# ExternalConnections.net
KiCad netlist of a schematic drawn in Altium Designer
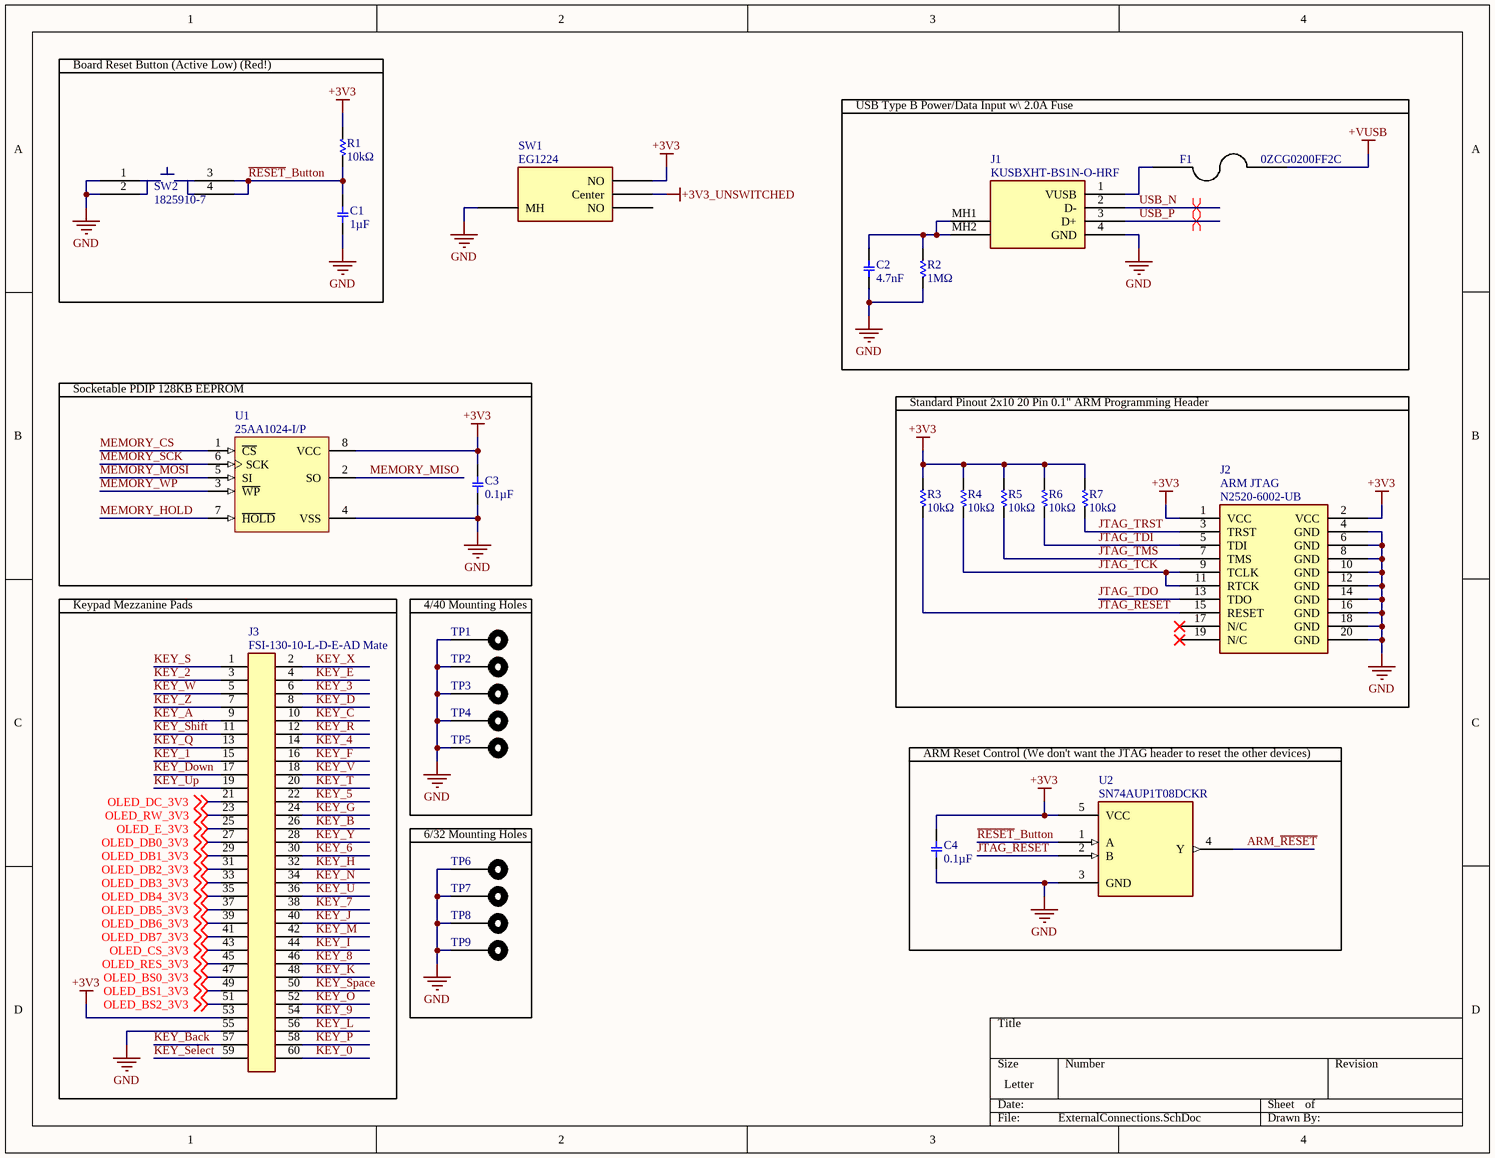
[diagram p0: ExternalConnections.SchDoc]

(export (version "E")
  (design (tool "Eeschema 10.0.6"))
  (components
    (comp (ref "C1")
      (value "1µF")
      (footprint "C0805(2012)_NP_med")
      (description "SMT Capacitor")
      (fields (field (name "TOLERANCE") "X7R"))
      (libsource (lib "ChipComponents") (part "CPN_SMT"))
    )
    (comp (ref "C2")
      (value "4.7nF")
      (footprint "C0805(2012)_NP_med")
      (description "SMT Capacitor")
      (fields (field (name "TOLERANCE") "X7R"))
      (libsource (lib "ChipComponents") (part "CPN_SMT"))
    )
    (comp (ref "C3")
      (value "0.1µF")
      (footprint "C0805(2012)_NP_med")
      (description "SMT Capacitor")
      (fields (field (name "TOLERANCE") "X7R"))
      (libsource (lib "ChipComponents") (part "CPN_SMT"))
    )
    (comp (ref "C4")
      (value "0.1µF")
      (footprint "C0805(2012)_NP_med")
      (description "SMT Capacitor")
      (fields (field (name "TOLERANCE") "X7R"))
      (libsource (lib "ChipComponents") (part "CPN_SMT"))
    )
    (comp (ref "F1")
      (value "Bel 0ZCG0200FF2C")
      (footprint "C1812(4532)_NP_med")
      (description "PTC RESTTBLE 2.0A 8V CHIP 1812")
      (fields
        (field (name "MANUFACTURER") "Bel Fuse Inc.")
        (field (name "MANUFACTURER PART NUMBER") "0ZCG0200FF2C")
      )
      (libsource (lib "RFIDSchematicLibrary") (part "Bel 0ZCG0200FF2C"))
    )
    (comp (ref "J1")
      (value "KUSBXHT-BS1N-O-HRF")
      (footprint "Kycon KUSBXHT-BS1N-O-HRF")
      (description "TYPE B ORANGE HIGH TEMP/RETENTION")
      (fields (field (name "MANUFACTURER") "Kycon"))
      (libsource (lib "RFIDSchematicLibrary") (part "Kycon KUSBXHT-BS1N-O-HRF"))
    )
    (comp (ref "J2")
      (value "ARM JTAG")
      (footprint "3M 2520-6002UB")
      (description "Standard 20-Pin Pinout")
      (fields (field (name "MANUFACTURER") "3M") (field (name "MANUFACTURER PART NUMBER") "N2520-6002-UB"))
      (libsource (lib "RFIDSchematicLibrary") (part "20-Pin ARM JTAG Programming Header"))
    )
    (comp (ref "J3")
      (value "FSI-130-10-L-D-E-AD Mate")
      (footprint "FSI-130-10-L-D-E-AD - Mate")
      (description "CONN INTERFACE ONE PC 1MM 60POS")
      (libsource (lib "RFIDSchematicLibrary") (part "Samtec FSI-130-10-L-D-E-AD Mate"))
    )
    (comp (ref "R1")
      (value "10kΩ")
      (footprint "R0805(2012)_med")
      (description "SMT resistor")
      (fields (field (name "TOLERANCE") "1%"))
      (libsource (lib "ChipComponents") (part "RES_SMT"))
    )
    (comp (ref "R2")
      (value "1MΩ")
      (footprint "R0805(2012)_med")
      (description "SMT resistor")
      (fields (field (name "TOLERANCE") "1%"))
      (libsource (lib "ChipComponents") (part "RES_SMT"))
    )
    (comp (ref "R3")
      (value "10kΩ")
      (footprint "R0805(2012)_med")
      (description "SMT resistor")
      (fields (field (name "TOLERANCE") "1%"))
      (libsource (lib "ChipComponents") (part "RES_SMT"))
    )
    (comp (ref "R4")
      (value "10kΩ")
      (footprint "R0805(2012)_med")
      (description "SMT resistor")
      (fields (field (name "TOLERANCE") "1%"))
      (libsource (lib "ChipComponents") (part "RES_SMT"))
    )
    (comp (ref "R5")
      (value "10kΩ")
      (footprint "R0805(2012)_med")
      (description "SMT resistor")
      (fields (field (name "TOLERANCE") "1%"))
      (libsource (lib "ChipComponents") (part "RES_SMT"))
    )
    (comp (ref "R6")
      (value "10kΩ")
      (footprint "R0805(2012)_med")
      (description "SMT resistor")
      (fields (field (name "TOLERANCE") "1%"))
      (libsource (lib "ChipComponents") (part "RES_SMT"))
    )
    (comp (ref "R7")
      (value "10kΩ")
      (footprint "R0805(2012)_med")
      (description "SMT resistor")
      (fields (field (name "TOLERANCE") "1%"))
      (libsource (lib "ChipComponents") (part "RES_SMT"))
    )
    (comp (ref "SW1")
      (value "E-Switch EG1224")
      (footprint "E-Switch EG1224")
      (description "SWITCH SLIDE SPDT 500MA 15V")
      (fields (field (name "MANUFACTURER") "E-Switch") (field (name "MANUFACTURER PART NUMBER") "EG1224"))
      (libsource (lib "RFIDSchematicLibrary") (part "E-Switch EG1224"))
    )
    (comp (ref "SW2")
      (value "1825910-7")
      (footprint "TE 1825910-6")
      (description "SWITCH TACTILE SPST-NO 0.05A 24V")
      (fields
        (field (name "MANUFACTURER") "TE Connectivity Alcoswitch Switches")
        (field (name "MANUFACTURER PART NUMBER") "1825910-6")
      )
      (libsource (lib "RFIDSchematicLibrary") (part "TE 1825910-6"))
    )
    (comp (ref "TP1")
      (value "Testpoint")
      (footprint "4-40 HOLE")
      (libsource (lib "RFIDSchematicLibrary") (part "Testpoint"))
    )
    (comp (ref "TP2")
      (value "Testpoint")
      (footprint "4-40 HOLE")
      (libsource (lib "RFIDSchematicLibrary") (part "Testpoint"))
    )
    (comp (ref "TP3")
      (value "Testpoint")
      (footprint "4-40 HOLE")
      (libsource (lib "RFIDSchematicLibrary") (part "Testpoint"))
    )
    (comp (ref "TP4")
      (value "Testpoint")
      (footprint "4-40 HOLE")
      (libsource (lib "RFIDSchematicLibrary") (part "Testpoint"))
    )
    (comp (ref "TP5")
      (value "Testpoint")
      (footprint "4-40 HOLE")
      (libsource (lib "RFIDSchematicLibrary") (part "Testpoint"))
    )
    (comp (ref "TP6")
      (value "Testpoint")
      (footprint "6-32 Hole")
      (libsource (lib "RFIDSchematicLibrary") (part "Testpoint"))
    )
    (comp (ref "TP7")
      (value "Testpoint")
      (footprint "6-32 Hole")
      (libsource (lib "RFIDSchematicLibrary") (part "Testpoint"))
    )
    (comp (ref "TP8")
      (value "Testpoint")
      (footprint "6-32 Hole")
      (libsource (lib "RFIDSchematicLibrary") (part "Testpoint"))
    )
    (comp (ref "TP9")
      (value "Testpoint")
      (footprint "6-32 Hole")
      (libsource (lib "RFIDSchematicLibrary") (part "Testpoint"))
    )
    (comp (ref "U1")
      (value "25AA1024-I/P")
      (footprint "PDIP300-P8")
      (description "1 Mbit SPI Bus Serial EEPROM, 8-Pin PDIP, Industrial Temperature")
      (fields (field (name "MANUFACTURER") "Microchip"))
      (libsource (lib "Microchip SPI Serial EEPROM") (part "25AA1024-I/P"))
    )
    (comp (ref "U2")
      (value "TI SN74AUP1T08DCKR")
      (footprint "TI 5 Pin DCK (R-PDSO-G5)")
      (description "IC GATE AND 1CH 2-INP SC-70-5")
      (fields
        (field (name "MANUFACTURER") "Texas Instruments")
        (field (name "MANUFACTURER PART NUMBER") "SN74AUP1T08DCKR")
      )
      (libsource (lib "RFIDSchematicLibrary") (part "TI SN74AUP1T08DCKR"))
    )
  )
  (nets
    (net (code "1") (name "+3V3") (class "Default")
      (node (ref "C3") (pin "1") (pinfunction "1_1") (pintype "passive"))
      (node (ref "C4") (pin "1") (pinfunction "1_1") (pintype "passive"))
      (node (ref "J2") (pin "1") (pinfunction "VCC_1") (pintype "passive"))
      (node (ref "J2") (pin "2") (pinfunction "VCC_2") (pintype "passive"))
      (node (ref "J3") (pin "53") (pinfunction "53_53") (pintype "passive"))
      (node (ref "R1") (pin "1") (pinfunction "1_1") (pintype "passive"))
      (node (ref "R3") (pin "1") (pinfunction "1_1") (pintype "passive"))
      (node (ref "R4") (pin "1") (pinfunction "1_1") (pintype "passive"))
      (node (ref "R5") (pin "1") (pinfunction "1_1") (pintype "passive"))
      (node (ref "R6") (pin "1") (pinfunction "1_1") (pintype "passive"))
      (node (ref "R7") (pin "1") (pinfunction "1_1") (pintype "passive"))
      (node (ref "SW1") (pin "1") (pinfunction "NO_1") (pintype "passive"))
      (node (ref "U1") (pin "8") (pinfunction "VCC_8") (pintype "power_in"))
      (node (ref "U2") (pin "5") (pinfunction "VCC_5") (pintype "power_in"))
    )
    (net (code "2") (name "+3V3_UNSWITCHED") (class "Default")
      (node (ref "SW1") (pin "2") (pinfunction "Center_2") (pintype "passive"))
    )
    (net (code "3") (name "+VUSB") (class "Default")
      (node (ref "F1") (pin "2") (pinfunction "2_2") (pintype "passive"))
    )
    (net (code "4") (name "/ARM_~{RESET}") (class "Default")
      (node (ref "U2") (pin "4") (pinfunction "Y_4") (pintype "output"))
    )
    (net (code "5") (name "/JTAG_TCK") (class "Default")
      (node (ref "J2") (pin "11") (pinfunction "RTCK_11") (pintype "passive"))
      (node (ref "J2") (pin "9") (pinfunction "TCLK_9") (pintype "passive"))
      (node (ref "R4") (pin "2") (pinfunction "2_2") (pintype "passive"))
    )
    (net (code "6") (name "/JTAG_TDI") (class "Default")
      (node (ref "J2") (pin "5") (pinfunction "TDI_5") (pintype "passive"))
      (node (ref "R6") (pin "2") (pinfunction "2_2") (pintype "passive"))
    )
    (net (code "7") (name "/JTAG_TDO") (class "Default")
      (node (ref "J2") (pin "13") (pinfunction "TDO_13") (pintype "passive"))
    )
    (net (code "8") (name "/JTAG_TMS") (class "Default")
      (node (ref "J2") (pin "7") (pinfunction "TMS_7") (pintype "passive"))
      (node (ref "R5") (pin "2") (pinfunction "2_2") (pintype "passive"))
    )
    (net (code "9") (name "/JTAG_TRST") (class "Default")
      (node (ref "J2") (pin "3") (pinfunction "TRST_3") (pintype "passive"))
      (node (ref "R7") (pin "2") (pinfunction "2_2") (pintype "passive"))
    )
    (net (code "10") (name "/JTAG_~{RESET}") (class "Default")
      (node (ref "J2") (pin "15") (pinfunction "RESET_15") (pintype "passive"))
      (node (ref "R3") (pin "2") (pinfunction "2_2") (pintype "passive"))
      (node (ref "U2") (pin "2") (pinfunction "B_2") (pintype "input"))
    )
    (net (code "11") (name "/KEY_0") (class "Default")
      (node (ref "J3") (pin "60") (pinfunction "60_60") (pintype "passive"))
    )
    (net (code "12") (name "/KEY_1") (class "Default")
      (node (ref "J3") (pin "15") (pinfunction "15_15") (pintype "passive"))
    )
    (net (code "13") (name "/KEY_2") (class "Default")
      (node (ref "J3") (pin "3") (pinfunction "3_3") (pintype "passive"))
    )
    (net (code "14") (name "/KEY_3") (class "Default")
      (node (ref "J3") (pin "6") (pinfunction "6_6") (pintype "passive"))
    )
    (net (code "15") (name "/KEY_4") (class "Default")
      (node (ref "J3") (pin "14") (pinfunction "14_14") (pintype "passive"))
    )
    (net (code "16") (name "/KEY_5") (class "Default")
      (node (ref "J3") (pin "22") (pinfunction "22_22") (pintype "passive"))
    )
    (net (code "17") (name "/KEY_6") (class "Default")
      (node (ref "J3") (pin "30") (pinfunction "30_30") (pintype "passive"))
    )
    (net (code "18") (name "/KEY_7") (class "Default")
      (node (ref "J3") (pin "38") (pinfunction "38_38") (pintype "passive"))
    )
    (net (code "19") (name "/KEY_8") (class "Default")
      (node (ref "J3") (pin "46") (pinfunction "46_46") (pintype "passive"))
    )
    (net (code "20") (name "/KEY_9") (class "Default")
      (node (ref "J3") (pin "54") (pinfunction "54_54") (pintype "passive"))
    )
    (net (code "21") (name "/KEY_A") (class "Default")
      (node (ref "J3") (pin "9") (pinfunction "9_9") (pintype "passive"))
    )
    (net (code "22") (name "/KEY_B") (class "Default")
      (node (ref "J3") (pin "26") (pinfunction "26_26") (pintype "passive"))
    )
    (net (code "23") (name "/KEY_Back") (class "Default")
      (node (ref "J3") (pin "57") (pinfunction "57_57") (pintype "passive"))
    )
    (net (code "24") (name "/KEY_C") (class "Default")
      (node (ref "J3") (pin "10") (pinfunction "10_10") (pintype "passive"))
    )
    (net (code "25") (name "/KEY_D") (class "Default")
      (node (ref "J3") (pin "8") (pinfunction "8_8") (pintype "passive"))
    )
    (net (code "26") (name "/KEY_Down") (class "Default")
      (node (ref "J3") (pin "17") (pinfunction "17_17") (pintype "passive"))
    )
    (net (code "27") (name "/KEY_E") (class "Default")
      (node (ref "J3") (pin "4") (pinfunction "4_4") (pintype "passive"))
    )
    (net (code "28") (name "/KEY_F") (class "Default")
      (node (ref "J3") (pin "16") (pinfunction "16_16") (pintype "passive"))
    )
    (net (code "29") (name "/KEY_G") (class "Default")
      (node (ref "J3") (pin "24") (pinfunction "24_24") (pintype "passive"))
    )
    (net (code "30") (name "/KEY_H") (class "Default")
      (node (ref "J3") (pin "32") (pinfunction "32_32") (pintype "passive"))
    )
    (net (code "31") (name "/KEY_I") (class "Default")
      (node (ref "J3") (pin "44") (pinfunction "44_44") (pintype "passive"))
    )
    (net (code "32") (name "/KEY_J") (class "Default")
      (node (ref "J3") (pin "40") (pinfunction "40_40") (pintype "passive"))
    )
    (net (code "33") (name "/KEY_K") (class "Default")
      (node (ref "J3") (pin "48") (pinfunction "48_48") (pintype "passive"))
    )
    (net (code "34") (name "/KEY_L") (class "Default")
      (node (ref "J3") (pin "56") (pinfunction "56_56") (pintype "passive"))
    )
    (net (code "35") (name "/KEY_M") (class "Default")
      (node (ref "J3") (pin "42") (pinfunction "42_42") (pintype "passive"))
    )
    (net (code "36") (name "/KEY_N") (class "Default")
      (node (ref "J3") (pin "34") (pinfunction "34_34") (pintype "passive"))
    )
    (net (code "37") (name "/KEY_O") (class "Default")
      (node (ref "J3") (pin "52") (pinfunction "52_52") (pintype "passive"))
    )
    (net (code "38") (name "/KEY_P") (class "Default")
      (node (ref "J3") (pin "58") (pinfunction "58_58") (pintype "passive"))
    )
    (net (code "39") (name "/KEY_Q") (class "Default")
      (node (ref "J3") (pin "13") (pinfunction "13_13") (pintype "passive"))
    )
    (net (code "40") (name "/KEY_R") (class "Default")
      (node (ref "J3") (pin "12") (pinfunction "12_12") (pintype "passive"))
    )
    (net (code "41") (name "/KEY_S") (class "Default")
      (node (ref "J3") (pin "1") (pinfunction "1_1") (pintype "passive"))
    )
    (net (code "42") (name "/KEY_Select") (class "Default")
      (node (ref "J3") (pin "59") (pinfunction "59_59") (pintype "passive"))
    )
    (net (code "43") (name "/KEY_Shift") (class "Default")
      (node (ref "J3") (pin "11") (pinfunction "11_11") (pintype "passive"))
    )
    (net (code "44") (name "/KEY_Space") (class "Default")
      (node (ref "J3") (pin "50") (pinfunction "50_50") (pintype "passive"))
    )
    (net (code "45") (name "/KEY_T") (class "Default")
      (node (ref "J3") (pin "20") (pinfunction "20_20") (pintype "passive"))
    )
    (net (code "46") (name "/KEY_U") (class "Default")
      (node (ref "J3") (pin "36") (pinfunction "36_36") (pintype "passive"))
    )
    (net (code "47") (name "/KEY_Up") (class "Default")
      (node (ref "J3") (pin "19") (pinfunction "19_19") (pintype "passive"))
    )
    (net (code "48") (name "/KEY_V") (class "Default")
      (node (ref "J3") (pin "18") (pinfunction "18_18") (pintype "passive"))
    )
    (net (code "49") (name "/KEY_W") (class "Default")
      (node (ref "J3") (pin "5") (pinfunction "5_5") (pintype "passive"))
    )
    (net (code "50") (name "/KEY_X") (class "Default")
      (node (ref "J3") (pin "2") (pinfunction "2_2") (pintype "passive"))
    )
    (net (code "51") (name "/KEY_Y") (class "Default")
      (node (ref "J3") (pin "28") (pinfunction "28_28") (pintype "passive"))
    )
    (net (code "52") (name "/KEY_Z") (class "Default")
      (node (ref "J3") (pin "7") (pinfunction "7_7") (pintype "passive"))
    )
    (net (code "53") (name "/MEMORY_CS") (class "Default")
      (node (ref "U1") (pin "1") (pinfunction "~{CS}_1") (pintype "input"))
    )
    (net (code "54") (name "/MEMORY_HOLD") (class "Default")
      (node (ref "U1") (pin "7") (pinfunction "~{HOLD}_7") (pintype "input"))
    )
    (net (code "55") (name "/MEMORY_MISO") (class "Default")
      (node (ref "U1") (pin "2") (pinfunction "SO_2") (pintype "tri_state"))
    )
    (net (code "56") (name "/MEMORY_MOSI") (class "Default")
      (node (ref "U1") (pin "5") (pinfunction "SI_5") (pintype "input"))
    )
    (net (code "57") (name "/MEMORY_SCK") (class "Default")
      (node (ref "U1") (pin "6") (pinfunction "SCK_6") (pintype "input"))
    )
    (net (code "58") (name "/MEMORY_WP") (class "Default")
      (node (ref "U1") (pin "3") (pinfunction "~{WP}_3") (pintype "input"))
    )
    (net (code "59") (name "/USB_N") (class "Default")
      (node (ref "J1") (pin "2") (pinfunction "D-_2") (pintype "passive"))
    )
    (net (code "60") (name "/USB_P") (class "Default")
      (node (ref "J1") (pin "3") (pinfunction "D+_3") (pintype "passive"))
    )
    (net (code "61") (name "/~{RESET}_Button") (class "Default")
      (node (ref "C1") (pin "1") (pinfunction "1_1") (pintype "passive"))
      (node (ref "R1") (pin "2") (pinfunction "2_2") (pintype "passive"))
      (node (ref "SW2") (pin "3") (pinfunction "3_3") (pintype "passive"))
      (node (ref "SW2") (pin "4") (pinfunction "4_4") (pintype "passive"))
      (node (ref "U2") (pin "1") (pinfunction "A_1") (pintype "input"))
    )
    (net (code "62") (name "GND") (class "Default")
      (node (ref "C1") (pin "2") (pinfunction "2_2") (pintype "passive"))
      (node (ref "C2") (pin "2") (pinfunction "2_2") (pintype "passive"))
      (node (ref "C3") (pin "2") (pinfunction "2_2") (pintype "passive"))
      (node (ref "C4") (pin "2") (pinfunction "2_2") (pintype "passive"))
      (node (ref "J1") (pin "4") (pinfunction "GND_4") (pintype "passive"))
      (node (ref "J2") (pin "10") (pinfunction "GND_10") (pintype "passive"))
      (node (ref "J2") (pin "12") (pinfunction "GND_12") (pintype "passive"))
      (node (ref "J2") (pin "14") (pinfunction "GND_14") (pintype "passive"))
      (node (ref "J2") (pin "16") (pinfunction "GND_16") (pintype "passive"))
      (node (ref "J2") (pin "18") (pinfunction "GND_18") (pintype "passive"))
      (node (ref "J2") (pin "20") (pinfunction "GND_20") (pintype "passive"))
      (node (ref "J2") (pin "4") (pinfunction "GND_4") (pintype "passive"))
      (node (ref "J2") (pin "6") (pinfunction "GND_6") (pintype "passive"))
      (node (ref "J2") (pin "8") (pinfunction "GND_8") (pintype "passive"))
      (node (ref "J3") (pin "55") (pinfunction "55_55") (pintype "passive"))
      (node (ref "R2") (pin "2") (pinfunction "2_2") (pintype "passive"))
      (node (ref "SW1") (pin "4") (pinfunction "MH_4") (pintype "passive"))
      (node (ref "SW2") (pin "1") (pinfunction "1_1") (pintype "passive"))
      (node (ref "SW2") (pin "2") (pinfunction "2_2") (pintype "passive"))
      (node (ref "TP1") (pin "1") (pinfunction "1_1") (pintype "passive"))
      (node (ref "TP2") (pin "1") (pinfunction "1_1") (pintype "passive"))
      (node (ref "TP3") (pin "1") (pinfunction "1_1") (pintype "passive"))
      (node (ref "TP4") (pin "1") (pinfunction "1_1") (pintype "passive"))
      (node (ref "TP5") (pin "1") (pinfunction "1_1") (pintype "passive"))
      (node (ref "TP6") (pin "1") (pinfunction "1_1") (pintype "passive"))
      (node (ref "TP7") (pin "1") (pinfunction "1_1") (pintype "passive"))
      (node (ref "TP8") (pin "1") (pinfunction "1_1") (pintype "passive"))
      (node (ref "TP9") (pin "1") (pinfunction "1_1") (pintype "passive"))
      (node (ref "U1") (pin "4") (pinfunction "VSS_4") (pintype "power_in"))
      (node (ref "U2") (pin "3") (pinfunction "GND_3") (pintype "power_in"))
    )
    (net (code "63") (name "Net-(C2-Pad1)") (class "Default")
      (node (ref "C2") (pin "1") (pinfunction "1_1") (pintype "passive"))
      (node (ref "J1") (pin "MH1") (pinfunction "MH1_MH1") (pintype "passive"))
      (node (ref "J1") (pin "MH2") (pinfunction "MH2_MH2") (pintype "passive"))
      (node (ref "R2") (pin "1") (pinfunction "1_1") (pintype "passive"))
    )
    (net (code "64") (name "Net-(J1-VUSB)") (class "Default")
      (node (ref "F1") (pin "1") (pinfunction "1_1") (pintype "passive"))
      (node (ref "J1") (pin "1") (pinfunction "VUSB_1") (pintype "passive"))
    )
    (net (code "65") (name "OLED_BS0_3V3") (class "Default")
      (node (ref "J3") (pin "47") (pinfunction "47_47") (pintype "passive"))
    )
    (net (code "66") (name "OLED_BS1_3V3") (class "Default")
      (node (ref "J3") (pin "49") (pinfunction "49_49") (pintype "passive"))
    )
    (net (code "67") (name "OLED_BS2_3V3") (class "Default")
      (node (ref "J3") (pin "51") (pinfunction "51_51") (pintype "passive"))
    )
    (net (code "68") (name "OLED_CS_3V3") (class "Default")
      (node (ref "J3") (pin "43") (pinfunction "43_43") (pintype "passive"))
    )
    (net (code "69") (name "OLED_DB0_3V3") (class "Default")
      (node (ref "J3") (pin "27") (pinfunction "27_27") (pintype "passive"))
    )
    (net (code "70") (name "OLED_DB1_3V3") (class "Default")
      (node (ref "J3") (pin "29") (pinfunction "29_29") (pintype "passive"))
    )
    (net (code "71") (name "OLED_DB2_3V3") (class "Default")
      (node (ref "J3") (pin "31") (pinfunction "31_31") (pintype "passive"))
    )
    (net (code "72") (name "OLED_DB3_3V3") (class "Default")
      (node (ref "J3") (pin "33") (pinfunction "33_33") (pintype "passive"))
    )
    (net (code "73") (name "OLED_DB4_3V3") (class "Default")
      (node (ref "J3") (pin "35") (pinfunction "35_35") (pintype "passive"))
    )
    (net (code "74") (name "OLED_DB5_3V3") (class "Default")
      (node (ref "J3") (pin "37") (pinfunction "37_37") (pintype "passive"))
    )
    (net (code "75") (name "OLED_DB6_3V3") (class "Default")
      (node (ref "J3") (pin "39") (pinfunction "39_39") (pintype "passive"))
    )
    (net (code "76") (name "OLED_DB7_3V3") (class "Default")
      (node (ref "J3") (pin "41") (pinfunction "41_41") (pintype "passive"))
    )
    (net (code "77") (name "OLED_DC_3V3") (class "Default")
      (node (ref "J3") (pin "21") (pinfunction "21_21") (pintype "passive"))
    )
    (net (code "78") (name "OLED_E_3V3") (class "Default")
      (node (ref "J3") (pin "25") (pinfunction "25_25") (pintype "passive"))
    )
    (net (code "79") (name "OLED_RES_3V3") (class "Default")
      (node (ref "J3") (pin "45") (pinfunction "45_45") (pintype "passive"))
    )
    (net (code "80") (name "OLED_RW_3V3") (class "Default")
      (node (ref "J3") (pin "23") (pinfunction "23_23") (pintype "passive"))
    )
    (net (code "81") (name "unconnected-(J2-N{slash}C-Pad17)") (class "Default")
      (node (ref "J2") (pin "17") (pinfunction "N/C_17") (pintype "passive+no_connect"))
    )
    (net (code "82") (name "unconnected-(J2-N{slash}C-Pad19)") (class "Default")
      (node (ref "J2") (pin "19") (pinfunction "N/C_19") (pintype "passive+no_connect"))
    )
    (net (code "83") (name "unconnected-(SW1-NO-Pad3)") (class "Default")
      (node (ref "SW1") (pin "3") (pinfunction "NO_3") (pintype "passive"))
    )
  )
)
